# CAN.net
KiCad netlist of a schematic drawn in Altium Designer
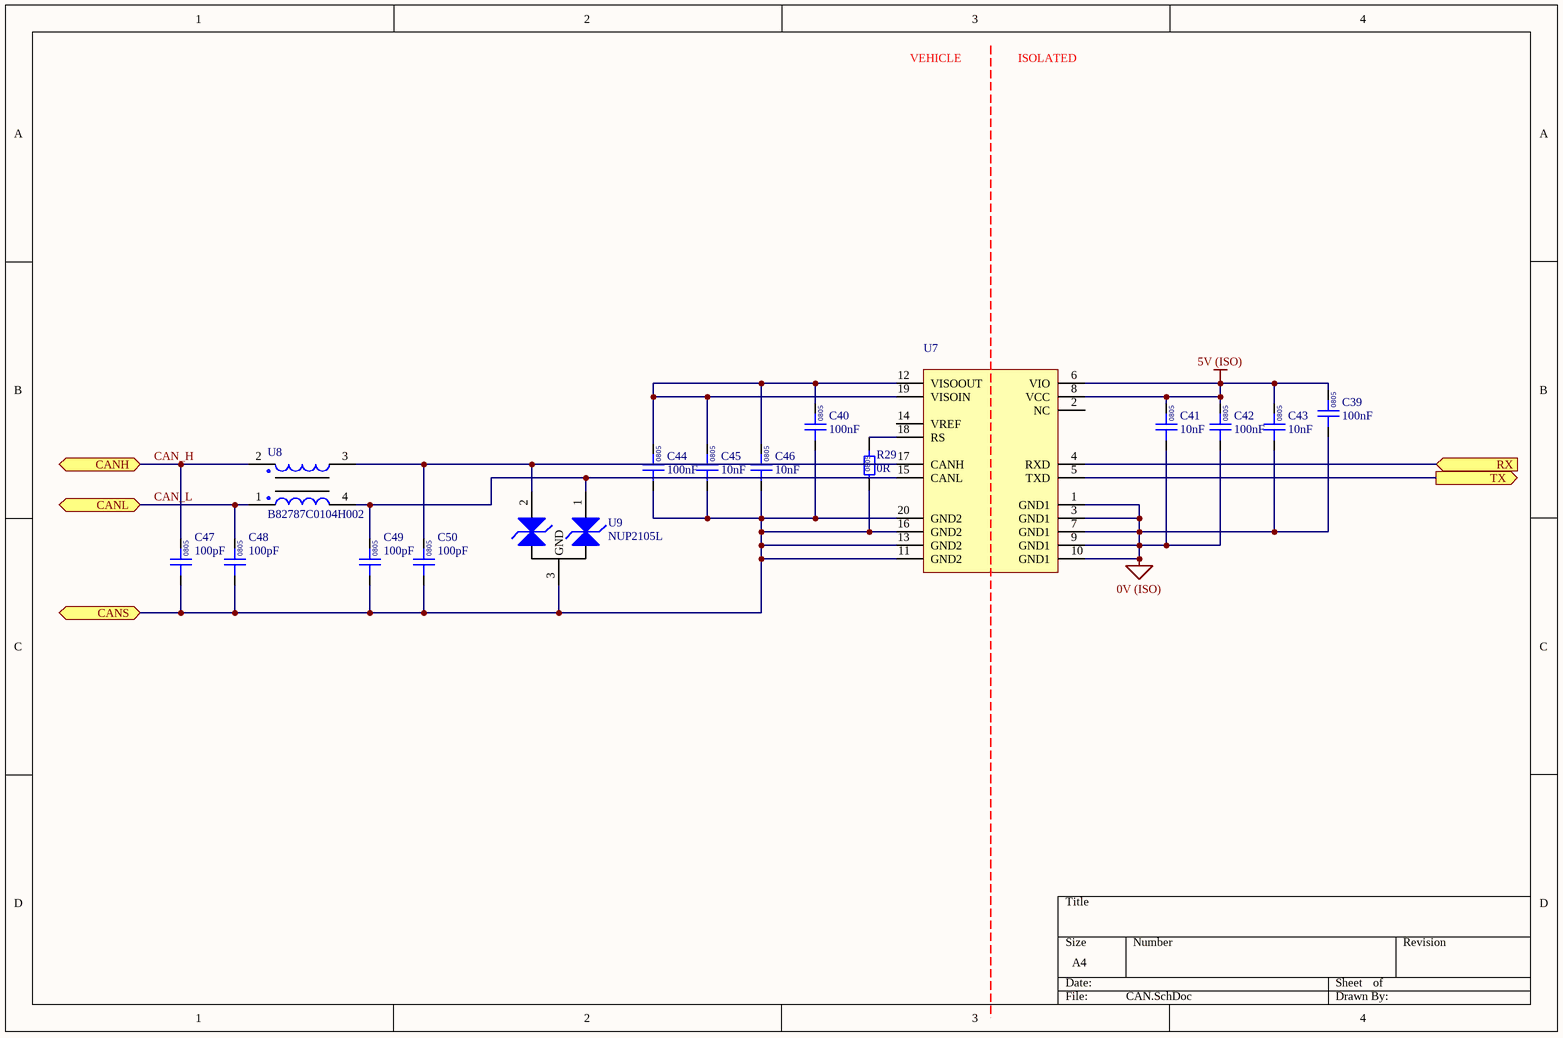
[diagram p0: CAN.SchDoc]

(export (version "E")
  (design (tool "Eeschema 10.0.6"))
  (components
    (comp (ref "C39")
      (value "100nF")
      (footprint "0805")
      (fields
        (field (name "PART NUMBER") "GCM21BR71H104KA37L")
        (field (name "TOLERANCE") "±10%")
        (field (name "MANUFACTURER") "muRata")
      )
      (libsource (lib "ts_standard_library") (part "Capacitor 0805"))
    )
    (comp (ref "C40")
      (value "100nF")
      (footprint "0805")
      (fields
        (field (name "PART NUMBER") "GCM21BR71H104KA37L")
        (field (name "TOLERANCE") "±10%")
        (field (name "MANUFACTURER") "muRata")
      )
      (libsource (lib "ts_standard_library") (part "Capacitor 0805"))
    )
    (comp (ref "C41")
      (value "10nF")
      (footprint "0805")
      (fields
        (field (name "PART NUMBER") "GCM2195C1H103JA16D")
        (field (name "TOLERANCE") "±5%")
        (field (name "MANUFACTURER") "muRata")
      )
      (libsource (lib "ts_standard_library") (part "Capacitor 0805"))
    )
    (comp (ref "C42")
      (value "100nF")
      (footprint "0805")
      (fields
        (field (name "PART NUMBER") "GCM21BR71H104KA37L")
        (field (name "TOLERANCE") "±10%")
        (field (name "MANUFACTURER") "muRata")
      )
      (libsource (lib "ts_standard_library") (part "Capacitor 0805"))
    )
    (comp (ref "C43")
      (value "10nF")
      (footprint "0805")
      (fields
        (field (name "PART NUMBER") "GCM2195C1H103JA16D")
        (field (name "TOLERANCE") "±5%")
        (field (name "MANUFACTURER") "muRata")
      )
      (libsource (lib "ts_standard_library") (part "Capacitor 0805"))
    )
    (comp (ref "C44")
      (value "100nF")
      (footprint "0805")
      (fields
        (field (name "PART NUMBER") "GCM21BR71H104KA37L")
        (field (name "TOLERANCE") "±10%")
        (field (name "MANUFACTURER") "muRata")
      )
      (libsource (lib "ts_standard_library") (part "Capacitor 0805"))
    )
    (comp (ref "C45")
      (value "10nF")
      (footprint "0805")
      (fields
        (field (name "PART NUMBER") "GCM2195C1H103JA16D")
        (field (name "TOLERANCE") "±5%")
        (field (name "MANUFACTURER") "muRata")
      )
      (libsource (lib "ts_standard_library") (part "Capacitor 0805"))
    )
    (comp (ref "C46")
      (value "10nF")
      (footprint "0805")
      (fields
        (field (name "PART NUMBER") "GCM2195C1H103JA16D")
        (field (name "TOLERANCE") "±5%")
        (field (name "MANUFACTURER") "muRata")
      )
      (libsource (lib "ts_standard_library") (part "Capacitor 0805"))
    )
    (comp (ref "C47")
      (value "100pF")
      (footprint "0805")
      (fields
        (field (name "PART NUMBER") "GCM2165C1H101JA16D")
        (field (name "TOLERANCE") "±5%")
        (field (name "MANUFACTURER") "muRata")
      )
      (libsource (lib "ts_standard_library") (part "Capacitor 0805"))
    )
    (comp (ref "C48")
      (value "100pF")
      (footprint "0805")
      (fields
        (field (name "PART NUMBER") "GCM2165C1H101JA16D")
        (field (name "TOLERANCE") "±5%")
        (field (name "MANUFACTURER") "muRata")
      )
      (libsource (lib "ts_standard_library") (part "Capacitor 0805"))
    )
    (comp (ref "C49")
      (value "100pF")
      (footprint "0805")
      (fields
        (field (name "PART NUMBER") "GCM2165C1H101JA16D")
        (field (name "TOLERANCE") "±5%")
        (field (name "MANUFACTURER") "muRata")
      )
      (libsource (lib "ts_standard_library") (part "Capacitor 0805"))
    )
    (comp (ref "C50")
      (value "100pF")
      (footprint "0805")
      (fields
        (field (name "PART NUMBER") "GCM2165C1H101JA16D")
        (field (name "TOLERANCE") "±5%")
        (field (name "MANUFACTURER") "muRata")
      )
      (libsource (lib "ts_standard_library") (part "Capacitor 0805"))
    )
    (comp (ref "R29")
      (value "0R")
      (footprint "0805")
      (fields
        (field (name "PART NUMBER") "RC0805FR070RL")
        (field (name "MANUFACTURER") "YAGEO")
        (field (name "TOLERANCE") "0.01")
      )
      (libsource (lib "ts_standard_library") (part "Resistor 0805"))
    )
    (comp (ref "U7")
      (value "~")
      (footprint "AD SOIC-W 20")
      (description "Isolated CAN Transceiver")
      (fields (field (name "PART NUMBER") "ADM3053") (field (name "MANUFACTURER") "Analogue Devices"))
      (libsource (lib "ts_standard_library") (part "ADM3053"))
    )
    (comp (ref "U8")
      (value "B82787C0104H002")
      (footprint "TDK 4-PC Pad")
      (fields
        (field (name "MANUFACTURER") "EPCOS (TDK)")
        (field (name "DIGIKEY PART NUMBER") "495-4598-1-ND")
      )
      (libsource (lib "ts_standard_library") (part "B82787C0104H002"))
    )
    (comp (ref "U9")
      (value "NUP2105L")
      (footprint "ON SOT-23")
      (description "Dual Line CAN Bus Protector")
      (fields
        (field (name "MANUFACTURER") "ON Semiconductor")
        (field (name "DIGIKEY PART NUMBER") "NUP2105LT1GOSCT-ND")
      )
      (libsource (lib "ts_standard_library") (part "NUP2105L"))
    )
  )
  (nets
    (net (code "1") (name "/CANS") (class "Default")
      (node (ref "C40") (pin "1") (pinfunction "1_1") (pintype "passive"))
      (node (ref "C44") (pin "1") (pinfunction "1_1") (pintype "passive"))
      (node (ref "C45") (pin "1") (pinfunction "1_1") (pintype "passive"))
      (node (ref "C46") (pin "1") (pinfunction "1_1") (pintype "passive"))
      (node (ref "C47") (pin "1") (pinfunction "1_1") (pintype "passive"))
      (node (ref "C48") (pin "1") (pinfunction "1_1") (pintype "passive"))
      (node (ref "C49") (pin "1") (pinfunction "1_1") (pintype "passive"))
      (node (ref "C50") (pin "1") (pinfunction "1_1") (pintype "passive"))
      (node (ref "R29") (pin "1") (pinfunction "1_1") (pintype "passive"))
      (node (ref "U7") (pin "11") (pinfunction "GND2_11") (pintype "passive"))
      (node (ref "U7") (pin "13") (pinfunction "GND2_13") (pintype "passive"))
      (node (ref "U7") (pin "16") (pinfunction "GND2_16") (pintype "passive"))
      (node (ref "U7") (pin "20") (pinfunction "GND2_20") (pintype "passive"))
      (node (ref "U9") (pin "3") (pinfunction "GND_3") (pintype "passive"))
    )
    (net (code "2") (name "/CAN_H") (class "Default")
      (node (ref "C47") (pin "2") (pinfunction "2_2") (pintype "passive"))
      (node (ref "U8") (pin "2") (pinfunction "2_2") (pintype "passive"))
    )
    (net (code "3") (name "/CAN_L") (class "Default")
      (node (ref "C48") (pin "2") (pinfunction "2_2") (pintype "passive"))
      (node (ref "U8") (pin "1") (pinfunction "1_1") (pintype "passive"))
    )
    (net (code "4") (name "/RX") (class "Default")
      (node (ref "U7") (pin "4") (pinfunction "RXD_4") (pintype "passive"))
    )
    (net (code "5") (name "/TX") (class "Default")
      (node (ref "U7") (pin "5") (pinfunction "TXD_5") (pintype "passive"))
    )
    (net (code "6") (name "0V (ISO)") (class "Default")
      (node (ref "C39") (pin "1") (pinfunction "1_1") (pintype "passive"))
      (node (ref "C41") (pin "1") (pinfunction "1_1") (pintype "passive"))
      (node (ref "C42") (pin "1") (pinfunction "1_1") (pintype "passive"))
      (node (ref "C43") (pin "1") (pinfunction "1_1") (pintype "passive"))
      (node (ref "U7") (pin "1") (pinfunction "GND1_1") (pintype "passive"))
      (node (ref "U7") (pin "10") (pinfunction "GND1_10") (pintype "passive"))
      (node (ref "U7") (pin "3") (pinfunction "GND1_3") (pintype "passive"))
      (node (ref "U7") (pin "7") (pinfunction "GND1_7") (pintype "passive"))
      (node (ref "U7") (pin "9") (pinfunction "GND1_9") (pintype "passive"))
    )
    (net (code "7") (name "5V (ISO)") (class "Default")
      (node (ref "C39") (pin "2") (pinfunction "2_2") (pintype "passive"))
      (node (ref "C41") (pin "2") (pinfunction "2_2") (pintype "passive"))
      (node (ref "C42") (pin "2") (pinfunction "2_2") (pintype "passive"))
      (node (ref "C43") (pin "2") (pinfunction "2_2") (pintype "passive"))
      (node (ref "U7") (pin "6") (pinfunction "VIO_6") (pintype "passive"))
      (node (ref "U7") (pin "8") (pinfunction "VCC_8") (pintype "passive"))
    )
    (net (code "8") (name "Net-(U7-CANH)") (class "Default")
      (node (ref "C50") (pin "2") (pinfunction "2_2") (pintype "passive"))
      (node (ref "U7") (pin "17") (pinfunction "CANH_17") (pintype "passive"))
      (node (ref "U8") (pin "3") (pinfunction "3_3") (pintype "passive"))
      (node (ref "U9") (pin "2") (pinfunction "CAN_L_2") (pintype "passive"))
    )
    (net (code "9") (name "Net-(U7-CANL)") (class "Default")
      (node (ref "C49") (pin "2") (pinfunction "2_2") (pintype "passive"))
      (node (ref "U7") (pin "15") (pinfunction "CANL_15") (pintype "passive"))
      (node (ref "U8") (pin "4") (pinfunction "4_4") (pintype "passive"))
      (node (ref "U9") (pin "1") (pinfunction "CAN_H_1") (pintype "passive"))
    )
    (net (code "10") (name "Net-(U7-RS)") (class "Default")
      (node (ref "R29") (pin "2") (pinfunction "2_2") (pintype "passive"))
      (node (ref "U7") (pin "18") (pinfunction "RS_18") (pintype "passive"))
    )
    (net (code "11") (name "Net-(U7-VISOIN)") (class "Default")
      (node (ref "C40") (pin "2") (pinfunction "2_2") (pintype "passive"))
      (node (ref "C44") (pin "2") (pinfunction "2_2") (pintype "passive"))
      (node (ref "C45") (pin "2") (pinfunction "2_2") (pintype "passive"))
      (node (ref "C46") (pin "2") (pinfunction "2_2") (pintype "passive"))
      (node (ref "U7") (pin "12") (pinfunction "VISOOUT_12") (pintype "passive"))
      (node (ref "U7") (pin "19") (pinfunction "VISOIN_19") (pintype "passive"))
    )
    (net (code "12") (name "unconnected-(U7-NC-Pad2)") (class "Default")
      (node (ref "U7") (pin "2") (pinfunction "NC_2") (pintype "passive"))
    )
    (net (code "13") (name "unconnected-(U7-VREF-Pad14)") (class "Default")
      (node (ref "U7") (pin "14") (pinfunction "VREF_14") (pintype "passive"))
    )
  )
)
